# 14_Ethernet.net
KiCad netlist of a schematic drawn in Altium Designer
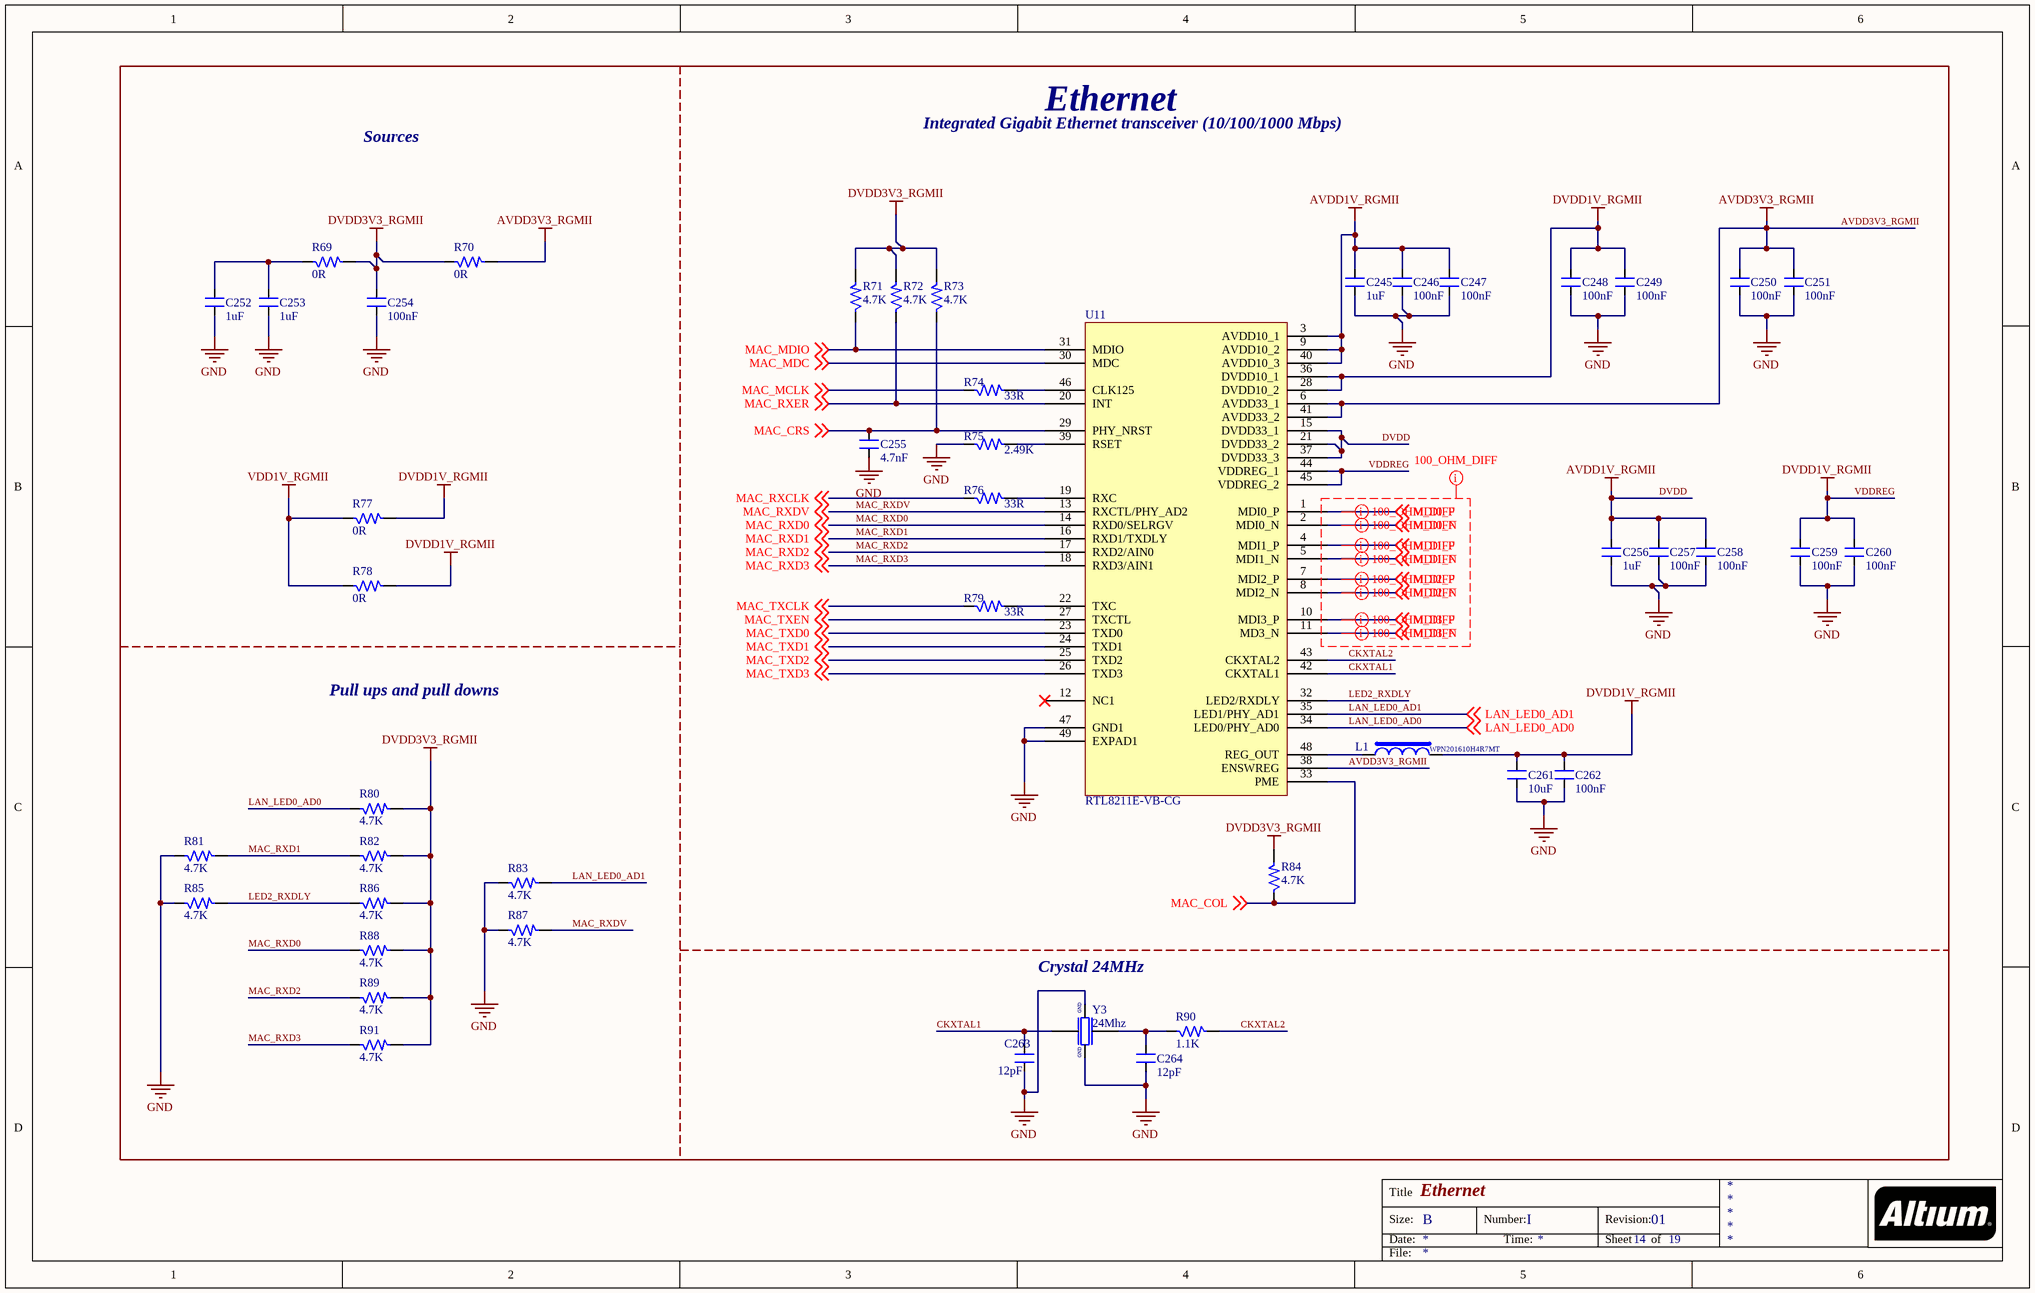
[diagram p0: [14] Ethernet.SchDoc]

(export (version "E")
  (design (tool "Eeschema 10.0.6"))
  (components
    (comp (ref "C245")
      (value "1uF")
      (footprint "CAP_0201")
      (description "1µF ±20% 16V Ceramic Capacitor X5R 0201 (0603 Metric)")
      (fields
        (field (name "MANUFACTURER") "Samsung Electro-Mechanics")
        (field (name "MANUFACTURER PART NUMBER") "CL03A105MO3NRNH")
      )
      (libsource (lib "EsteemPCB_SOM_Course_intlib") (part "CAP_1uF-16V-10%-0201"))
    )
    (comp (ref "C246")
      (value "100nF")
      (footprint "CAP_0201")
      (description "0.1µF ±10% 25V Ceramic Capacitor X5R 0201 (0603 Metric)")
      (fields
        (field (name "MANUFACTURER") "TDK Corporation")
        (field (name "MANUFACTURER PART NUMBER") "C0603X5R1E104K030BB")
      )
      (libsource (lib "EsteemPCB_SOM_Course_intlib") (part "CAP_100nF-25V-10%-0201"))
    )
    (comp (ref "C247")
      (value "100nF")
      (footprint "CAP_0201")
      (description "0.1µF ±10% 25V Ceramic Capacitor X5R 0201 (0603 Metric)")
      (fields
        (field (name "MANUFACTURER") "TDK Corporation")
        (field (name "MANUFACTURER PART NUMBER") "C0603X5R1E104K030BB")
      )
      (libsource (lib "EsteemPCB_SOM_Course_intlib") (part "CAP_100nF-25V-10%-0201"))
    )
    (comp (ref "C248")
      (value "100nF")
      (footprint "CAP_0201")
      (description "0.1µF ±10% 25V Ceramic Capacitor X5R 0201 (0603 Metric)")
      (fields
        (field (name "MANUFACTURER") "TDK Corporation")
        (field (name "MANUFACTURER PART NUMBER") "C0603X5R1E104K030BB")
      )
      (libsource (lib "EsteemPCB_SOM_Course_intlib") (part "CAP_100nF-25V-10%-0201"))
    )
    (comp (ref "C249")
      (value "100nF")
      (footprint "CAP_0201")
      (description "0.1µF ±10% 25V Ceramic Capacitor X5R 0201 (0603 Metric)")
      (fields
        (field (name "MANUFACTURER") "TDK Corporation")
        (field (name "MANUFACTURER PART NUMBER") "C0603X5R1E104K030BB")
      )
      (libsource (lib "EsteemPCB_SOM_Course_intlib") (part "CAP_100nF-25V-10%-0201"))
    )
    (comp (ref "C250")
      (value "100nF")
      (footprint "CAP_0201")
      (description "0.1µF ±10% 25V Ceramic Capacitor X5R 0201 (0603 Metric)")
      (fields
        (field (name "MANUFACTURER") "TDK Corporation")
        (field (name "MANUFACTURER PART NUMBER") "C0603X5R1E104K030BB")
      )
      (libsource (lib "EsteemPCB_SOM_Course_intlib") (part "CAP_100nF-25V-10%-0201"))
    )
    (comp (ref "C251")
      (value "100nF")
      (footprint "CAP_0201")
      (description "0.1µF ±10% 25V Ceramic Capacitor X5R 0201 (0603 Metric)")
      (fields
        (field (name "MANUFACTURER") "TDK Corporation")
        (field (name "MANUFACTURER PART NUMBER") "C0603X5R1E104K030BB")
      )
      (libsource (lib "EsteemPCB_SOM_Course_intlib") (part "CAP_100nF-25V-10%-0201"))
    )
    (comp (ref "C252")
      (value "1uF")
      (footprint "CAP_0402")
      (description "1µF ±10% 16V Ceramic Capacitor X5R 0402 (1005 Metric)")
      (fields
        (field (name "MANUFACTURER") "Knowles Novacap")
        (field (name "MANUFACTURER PART NUMBER") "0402BW105K160YT")
      )
      (libsource (lib "EsteemPCB_SOM_Course_intlib") (part "CAP_1uF-16V-10%-0402"))
    )
    (comp (ref "C253")
      (value "1uF")
      (footprint "CAP_0402")
      (description "1µF ±10% 16V Ceramic Capacitor X5R 0402 (1005 Metric)")
      (fields
        (field (name "MANUFACTURER") "Knowles Novacap")
        (field (name "MANUFACTURER PART NUMBER") "0402BW105K160YT")
      )
      (libsource (lib "EsteemPCB_SOM_Course_intlib") (part "CAP_1uF-16V-10%-0402"))
    )
    (comp (ref "C254")
      (value "100nF")
      (footprint "CAP_0201")
      (description "0.1µF ±10% 25V Ceramic Capacitor X5R 0201 (0603 Metric)")
      (fields
        (field (name "MANUFACTURER") "TDK Corporation")
        (field (name "MANUFACTURER PART NUMBER") "C0603X5R1E104K030BB")
      )
      (libsource (lib "EsteemPCB_SOM_Course_intlib") (part "CAP_100nF-25V-10%-0201"))
    )
    (comp (ref "C255")
      (value "4.7nF")
      (footprint "CAP_0201")
      (description "4700pF ±10% 10V Ceramic Capacitor X7R 0201 (0603 Metric)")
      (fields
        (field (name "MANUFACTURER") "AVX Corporation")
        (field (name "MANUFACTURER PART NUMBER") "0201ZC472KAT2A")
      )
      (libsource (lib "EsteemPCB_SOM_Course_intlib") (part "CAP_4.7nF-10V-10%-0201"))
    )
    (comp (ref "C256")
      (value "1uF")
      (footprint "CAP_0201")
      (description "1µF ±20% 16V Ceramic Capacitor X5R 0201 (0603 Metric)")
      (fields
        (field (name "MANUFACTURER") "Samsung Electro-Mechanics")
        (field (name "MANUFACTURER PART NUMBER") "CL03A105MO3NRNH")
      )
      (libsource (lib "EsteemPCB_SOM_Course_intlib") (part "CAP_1uF-16V-10%-0201"))
    )
    (comp (ref "C257")
      (value "100nF")
      (footprint "CAP_0201")
      (description "0.1µF ±10% 25V Ceramic Capacitor X5R 0201 (0603 Metric)")
      (fields
        (field (name "MANUFACTURER") "TDK Corporation")
        (field (name "MANUFACTURER PART NUMBER") "C0603X5R1E104K030BB")
      )
      (libsource (lib "EsteemPCB_SOM_Course_intlib") (part "CAP_100nF-25V-10%-0201"))
    )
    (comp (ref "C258")
      (value "100nF")
      (footprint "CAP_0201")
      (description "0.1µF ±10% 25V Ceramic Capacitor X5R 0201 (0603 Metric)")
      (fields
        (field (name "MANUFACTURER") "TDK Corporation")
        (field (name "MANUFACTURER PART NUMBER") "C0603X5R1E104K030BB")
      )
      (libsource (lib "EsteemPCB_SOM_Course_intlib") (part "CAP_100nF-25V-10%-0201"))
    )
    (comp (ref "C259")
      (value "100nF")
      (footprint "CAP_0201")
      (description "0.1µF ±10% 25V Ceramic Capacitor X5R 0201 (0603 Metric)")
      (fields
        (field (name "MANUFACTURER") "TDK Corporation")
        (field (name "MANUFACTURER PART NUMBER") "C0603X5R1E104K030BB")
      )
      (libsource (lib "EsteemPCB_SOM_Course_intlib") (part "CAP_100nF-25V-10%-0201"))
    )
    (comp (ref "C260")
      (value "100nF")
      (footprint "CAP_0201")
      (description "0.1µF ±10% 25V Ceramic Capacitor X5R 0201 (0603 Metric)")
      (fields
        (field (name "MANUFACTURER") "TDK Corporation")
        (field (name "MANUFACTURER PART NUMBER") "C0603X5R1E104K030BB")
      )
      (libsource (lib "EsteemPCB_SOM_Course_intlib") (part "CAP_100nF-25V-10%-0201"))
    )
    (comp (ref "C261")
      (value "10uF")
      (footprint "CAP_0402")
      (description "10µF ±20% 10V Ceramic Capacitor X5R 0402 (1005 Metric)")
      (fields
        (field (name "MANUFACTURER PART NUMBER") "CL05A106MP5NUNC")
        (field (name "MANUFACTURER") "Samsung Electro-Mechanics")
      )
      (libsource (lib "EsteemPCB_SOM_Course_intlib") (part "CAP_10uF-10V-20%-0402"))
    )
    (comp (ref "C262")
      (value "100nF")
      (footprint "CAP_0201")
      (description "0.1µF ±10% 25V Ceramic Capacitor X5R 0201 (0603 Metric)")
      (fields
        (field (name "MANUFACTURER") "TDK Corporation")
        (field (name "MANUFACTURER PART NUMBER") "C0603X5R1E104K030BB")
      )
      (libsource (lib "EsteemPCB_SOM_Course_intlib") (part "CAP_100nF-25V-10%-0201"))
    )
    (comp (ref "C263")
      (value "12pF")
      (footprint "CAP_0402")
      (description "12pF ±10% 10V Ceramic Capacitor X8R 0402 (1005 Metric)")
      (fields
        (field (name "MANUFACTURER") "KEMET")
        (field (name "MANUFACTURER PART NUMBER") "C0402C120K8HAC7867")
      )
      (libsource (lib "EsteemPCB_SOM_Course_intlib") (part "CAP_12pF-10V-10%-0402"))
    )
    (comp (ref "C264")
      (value "12pF")
      (footprint "CAP_0402")
      (description "12pF ±10% 10V Ceramic Capacitor X8R 0402 (1005 Metric)")
      (fields
        (field (name "MANUFACTURER") "KEMET")
        (field (name "MANUFACTURER PART NUMBER") "C0402C120K8HAC7867")
      )
      (libsource (lib "EsteemPCB_SOM_Course_intlib") (part "CAP_12pF-10V-10%-0402"))
    )
    (comp (ref "L1")
      (value "WPN201610H4R7MT")
      (footprint "IND_62.9_110X86.6_SMD")
      (description "4.7uH ±20% 900mA 425mΩ SMD,2.0x1.6x1.0mm Power Inductors RoHS")
      (fields (field (name "MANUFACTURER") "Sunlord"))
      (libsource (lib "EsteemPCB_SOM_Course_intlib") (part "IND_4.7uH-0.9A-20%-SMD"))
    )
    (comp (ref "R69")
      (value "0R")
      (footprint "RES_0201")
      (description "0 Ohms Jumper 0.05W, 1/20W Chip Resistor 0201 (0603 Metric) Automotive AEC-Q200 Thick Film")
      (fields
        (field (name "MANUFACTURER") "Bourns Inc.")
        (field (name "MANUFACTURER PART NUMBER") "CR0201AJ/-000GLF")
      )
      (libsource (lib "EsteemPCB_SOM_Course_intlib") (part "RES_0R-0.05W-1%-0201"))
    )
    (comp (ref "R70")
      (value "0R")
      (footprint "RES_0201")
      (description "0 Ohms Jumper 0.05W, 1/20W Chip Resistor 0201 (0603 Metric) Automotive AEC-Q200 Thick Film")
      (fields
        (field (name "MANUFACTURER") "Bourns Inc.")
        (field (name "MANUFACTURER PART NUMBER") "CR0201AJ/-000GLF")
      )
      (libsource (lib "EsteemPCB_SOM_Course_intlib") (part "RES_0R-0.05W-1%-0201"))
    )
    (comp (ref "R71")
      (value "4.7K")
      (footprint "RES_0201")
      (description "4.02 kOhms ±1% 0.05W, 1/20W Chip Resistor 0201 (0603 Metric) Thick Film")
      (fields
        (field (name "MANUFACTURER") "Yageo")
        (field (name "MANUFACTURER PART NUMBER") "RC0201FR-074K02L")
      )
      (libsource (lib "EsteemPCB_SOM_Course_intlib") (part "RES_4.7K-0.1W-1%-0201"))
    )
    (comp (ref "R72")
      (value "4.7K")
      (footprint "RES_0201")
      (description "4.02 kOhms ±1% 0.05W, 1/20W Chip Resistor 0201 (0603 Metric) Thick Film")
      (fields
        (field (name "MANUFACTURER") "Yageo")
        (field (name "MANUFACTURER PART NUMBER") "RC0201FR-074K02L")
      )
      (libsource (lib "EsteemPCB_SOM_Course_intlib") (part "RES_4.7K-0.1W-1%-0201"))
    )
    (comp (ref "R73")
      (value "4.7K")
      (footprint "RES_0201")
      (description "4.02 kOhms ±1% 0.05W, 1/20W Chip Resistor 0201 (0603 Metric) Thick Film")
      (fields
        (field (name "MANUFACTURER") "Yageo")
        (field (name "MANUFACTURER PART NUMBER") "RC0201FR-074K02L")
      )
      (libsource (lib "EsteemPCB_SOM_Course_intlib") (part "RES_4.7K-0.1W-1%-0201"))
    )
    (comp (ref "R74")
      (value "33R")
      (footprint "RES_0201")
      (description "33 Ohms ±1% 0.05W, 1/20W Chip Resistor 0201 (0603 Metric) Thick Film")
      (fields
        (field (name "MANUFACTURER") "Yageo")
        (field (name "MANUFACTURER PART NUMBER") "RC0201FR-0733RL")
      )
      (libsource (lib "EsteemPCB_SOM_Course_intlib") (part "RES_33R-0.05W-1%-0201"))
    )
    (comp (ref "R75")
      (value "2.49K")
      (footprint "RES_0201")
      (description "2.49 kOhms ±1% 0.05W, 1/20W Chip Resistor 0201 (0603 Metric) Automotive AEC-Q200 Thick Film")
      (fields
        (field (name "MANUFACTURER") "Panasonic Electronic Components")
        (field (name "MANUFACTURER PART NUMBER") "ERJ-1GNF2491C")
      )
      (libsource (lib "EsteemPCB_SOM_Course_intlib") (part "RES_2.49K-0.05W-1%-0201"))
    )
    (comp (ref "R76")
      (value "33R")
      (footprint "RES_0201")
      (description "33 Ohms ±1% 0.05W, 1/20W Chip Resistor 0201 (0603 Metric) Thick Film")
      (fields
        (field (name "MANUFACTURER") "Yageo")
        (field (name "MANUFACTURER PART NUMBER") "RC0201FR-0733RL")
      )
      (libsource (lib "EsteemPCB_SOM_Course_intlib") (part "RES_33R-0.05W-1%-0201"))
    )
    (comp (ref "R77")
      (value "0R")
      (footprint "RES_0201")
      (description "0 Ohms Jumper 0.05W, 1/20W Chip Resistor 0201 (0603 Metric) Automotive AEC-Q200 Thick Film")
      (fields
        (field (name "MANUFACTURER") "Bourns Inc.")
        (field (name "MANUFACTURER PART NUMBER") "CR0201AJ/-000GLF")
      )
      (libsource (lib "EsteemPCB_SOM_Course_intlib") (part "RES_0R-0.05W-1%-0201"))
    )
    (comp (ref "R78")
      (value "0R")
      (footprint "RES_0201")
      (description "0 Ohms Jumper 0.05W, 1/20W Chip Resistor 0201 (0603 Metric) Automotive AEC-Q200 Thick Film")
      (fields
        (field (name "MANUFACTURER") "Bourns Inc.")
        (field (name "MANUFACTURER PART NUMBER") "CR0201AJ/-000GLF")
      )
      (libsource (lib "EsteemPCB_SOM_Course_intlib") (part "RES_0R-0.05W-1%-0201"))
    )
    (comp (ref "R79")
      (value "33R")
      (footprint "RES_0201")
      (description "33 Ohms ±1% 0.05W, 1/20W Chip Resistor 0201 (0603 Metric) Thick Film")
      (fields
        (field (name "MANUFACTURER") "Yageo")
        (field (name "MANUFACTURER PART NUMBER") "RC0201FR-0733RL")
      )
      (libsource (lib "EsteemPCB_SOM_Course_intlib") (part "RES_33R-0.05W-1%-0201"))
    )
    (comp (ref "R80")
      (value "4.7K")
      (footprint "RES_0201")
      (description "4.02 kOhms ±1% 0.05W, 1/20W Chip Resistor 0201 (0603 Metric) Thick Film")
      (fields
        (field (name "MANUFACTURER") "Yageo")
        (field (name "MANUFACTURER PART NUMBER") "RC0201FR-074K02L")
      )
      (libsource (lib "EsteemPCB_SOM_Course_intlib") (part "RES_4.7K-0.1W-1%-0201"))
    )
    (comp (ref "R81")
      (value "4.7K")
      (footprint "RES_0201")
      (description "4.02 kOhms ±1% 0.05W, 1/20W Chip Resistor 0201 (0603 Metric) Thick Film")
      (fields
        (field (name "MANUFACTURER") "Yageo")
        (field (name "MANUFACTURER PART NUMBER") "RC0201FR-074K02L")
      )
      (libsource (lib "EsteemPCB_SOM_Course_intlib") (part "RES_4.7K-0.1W-1%-0201"))
    )
    (comp (ref "R82")
      (value "4.7K")
      (footprint "RES_0201")
      (description "4.02 kOhms ±1% 0.05W, 1/20W Chip Resistor 0201 (0603 Metric) Thick Film")
      (fields
        (field (name "MANUFACTURER") "Yageo")
        (field (name "MANUFACTURER PART NUMBER") "RC0201FR-074K02L")
      )
      (libsource (lib "EsteemPCB_SOM_Course_intlib") (part "RES_4.7K-0.1W-1%-0201"))
    )
    (comp (ref "R83")
      (value "4.7K")
      (footprint "RES_0201")
      (description "4.02 kOhms ±1% 0.05W, 1/20W Chip Resistor 0201 (0603 Metric) Thick Film")
      (fields
        (field (name "MANUFACTURER") "Yageo")
        (field (name "MANUFACTURER PART NUMBER") "RC0201FR-074K02L")
      )
      (libsource (lib "EsteemPCB_SOM_Course_intlib") (part "RES_4.7K-0.1W-1%-0201"))
    )
    (comp (ref "R84")
      (value "4.7K")
      (footprint "RES_0201")
      (description "4.02 kOhms ±1% 0.05W, 1/20W Chip Resistor 0201 (0603 Metric) Thick Film")
      (fields
        (field (name "MANUFACTURER") "Yageo")
        (field (name "MANUFACTURER PART NUMBER") "RC0201FR-074K02L")
      )
      (libsource (lib "EsteemPCB_SOM_Course_intlib") (part "RES_4.7K-0.1W-1%-0201"))
    )
    (comp (ref "R85")
      (value "4.7K")
      (footprint "RES_0201")
      (description "4.02 kOhms ±1% 0.05W, 1/20W Chip Resistor 0201 (0603 Metric) Thick Film")
      (fields
        (field (name "MANUFACTURER") "Yageo")
        (field (name "MANUFACTURER PART NUMBER") "RC0201FR-074K02L")
      )
      (libsource (lib "EsteemPCB_SOM_Course_intlib") (part "RES_4.7K-0.1W-1%-0201"))
    )
    (comp (ref "R86")
      (value "4.7K")
      (footprint "RES_0201")
      (description "4.02 kOhms ±1% 0.05W, 1/20W Chip Resistor 0201 (0603 Metric) Thick Film")
      (fields
        (field (name "MANUFACTURER") "Yageo")
        (field (name "MANUFACTURER PART NUMBER") "RC0201FR-074K02L")
      )
      (libsource (lib "EsteemPCB_SOM_Course_intlib") (part "RES_4.7K-0.1W-1%-0201"))
    )
    (comp (ref "R87")
      (value "4.7K")
      (footprint "RES_0201")
      (description "4.02 kOhms ±1% 0.05W, 1/20W Chip Resistor 0201 (0603 Metric) Thick Film")
      (fields
        (field (name "MANUFACTURER") "Yageo")
        (field (name "MANUFACTURER PART NUMBER") "RC0201FR-074K02L")
      )
      (libsource (lib "EsteemPCB_SOM_Course_intlib") (part "RES_4.7K-0.1W-1%-0201"))
    )
    (comp (ref "R88")
      (value "4.7K")
      (footprint "RES_0201")
      (description "4.02 kOhms ±1% 0.05W, 1/20W Chip Resistor 0201 (0603 Metric) Thick Film")
      (fields
        (field (name "MANUFACTURER") "Yageo")
        (field (name "MANUFACTURER PART NUMBER") "RC0201FR-074K02L")
      )
      (libsource (lib "EsteemPCB_SOM_Course_intlib") (part "RES_4.7K-0.1W-1%-0201"))
    )
    (comp (ref "R89")
      (value "4.7K")
      (footprint "RES_0201")
      (description "4.02 kOhms ±1% 0.05W, 1/20W Chip Resistor 0201 (0603 Metric) Thick Film")
      (fields
        (field (name "MANUFACTURER") "Yageo")
        (field (name "MANUFACTURER PART NUMBER") "RC0201FR-074K02L")
      )
      (libsource (lib "EsteemPCB_SOM_Course_intlib") (part "RES_4.7K-0.1W-1%-0201"))
    )
    (comp (ref "R90")
      (value "1.1K")
      (footprint "RES_0201")
      (description "1.1 kOhms ±1% 0.05W, 1/20W Chip Resistor 0201 (0603 Metric) Automotive AEC-Q200 Thick Film")
      (fields
        (field (name "MANUFACTURER") "Panasonic Electronic Components")
        (field (name "MANUFACTURER PART NUMBER") "ERJ-1GNF1101C")
      )
      (libsource (lib "EsteemPCB_SOM_Course_intlib") (part "RES_1.1K-0.05W-1%-0201"))
    )
    (comp (ref "R91")
      (value "4.7K")
      (footprint "RES_0201")
      (description "4.02 kOhms ±1% 0.05W, 1/20W Chip Resistor 0201 (0603 Metric) Thick Film")
      (fields
        (field (name "MANUFACTURER") "Yageo")
        (field (name "MANUFACTURER PART NUMBER") "RC0201FR-074K02L")
      )
      (libsource (lib "EsteemPCB_SOM_Course_intlib") (part "RES_4.7K-0.1W-1%-0201"))
    )
    (comp (ref "U11")
      (value "RTL8211E-VB-CG")
      (footprint "QFN48_19.6_324X324_SMD")
      (fields (field (name "MANUFACTURER") "Realtek Semicon"))
      (libsource (lib "EsteemPCB_SOM_Course_intlib") (part "IC_RTL8211E-VB-CG"))
    )
    (comp (ref "Y3")
      (value "24Mhz")
      (footprint "XTAL_ABM8AIG-24.000MHZ-12-2Z-T3")
      (description "24MHz ±20ppm Crystal 12pF 50 Ohms 4-SMD, No Lead")
      (fields
        (field (name "MANUFACTURER") "Abracon LLC")
        (field (name "MANUFACTURER PART NUMBER") "ABM8AIG-24.000MHZ-12-2Z-T3")
      )
      (libsource (lib "EsteemPCB_SOM_Course_intlib") (part "XTAL_24Mhz-12pF-4-SMD"))
    )
  )
  (nets
    (net (code "1") (name "/CKXTAL1") (class "Default")
      (node (ref "C263") (pin "2") (pinfunction "2_2") (pintype "passive"))
      (node (ref "U11") (pin "42") (pinfunction "CKXTAL1_42") (pintype "passive"))
      (node (ref "Y3") (pin "1") (pinfunction "1_1") (pintype "passive"))
    )
    (net (code "2") (name "/CKXTAL2") (class "Default")
      (node (ref "R90") (pin "2") (pinfunction "2_2") (pintype "passive"))
      (node (ref "U11") (pin "43") (pinfunction "CKXTAL2_43") (pintype "passive"))
    )
    (net (code "3") (name "/LED2_RXDLY") (class "Default")
      (node (ref "R85") (pin "2") (pinfunction "2_2") (pintype "passive"))
      (node (ref "R86") (pin "1") (pinfunction "1_1") (pintype "passive"))
      (node (ref "U11") (pin "32") (pinfunction "LED2/RXDLY_32") (pintype "passive"))
    )
    (net (code "4") (name "AVDD1V_RGMII") (class "Default")
      (node (ref "C245") (pin "2") (pinfunction "2_2") (pintype "passive"))
      (node (ref "C246") (pin "2") (pinfunction "2_2") (pintype "passive"))
      (node (ref "C247") (pin "2") (pinfunction "2_2") (pintype "passive"))
      (node (ref "C256") (pin "2") (pinfunction "2_2") (pintype "passive"))
      (node (ref "C257") (pin "2") (pinfunction "2_2") (pintype "passive"))
      (node (ref "C258") (pin "2") (pinfunction "2_2") (pintype "passive"))
      (node (ref "U11") (pin "15") (pinfunction "DVDD33_1_15") (pintype "passive"))
      (node (ref "U11") (pin "21") (pinfunction "DVDD33_2_21") (pintype "passive"))
      (node (ref "U11") (pin "3") (pinfunction "AVDD10_1_3") (pintype "passive"))
      (node (ref "U11") (pin "37") (pinfunction "DVDD33_3_37") (pintype "passive"))
      (node (ref "U11") (pin "40") (pinfunction "AVDD10_3_40") (pintype "passive"))
      (node (ref "U11") (pin "9") (pinfunction "AVDD10_2_9") (pintype "passive"))
    )
    (net (code "5") (name "AVDD3V3_RGMII") (class "Default")
      (node (ref "C250") (pin "2") (pinfunction "2_2") (pintype "passive"))
      (node (ref "C251") (pin "2") (pinfunction "2_2") (pintype "passive"))
      (node (ref "R70") (pin "2") (pinfunction "2_2") (pintype "passive"))
      (node (ref "U11") (pin "38") (pinfunction "ENSWREG_38") (pintype "passive"))
      (node (ref "U11") (pin "41") (pinfunction "AVDD33_2_41") (pintype "passive"))
      (node (ref "U11") (pin "6") (pinfunction "AVDD33_1_6") (pintype "passive"))
    )
    (net (code "6") (name "DVDD1V_RGMII") (class "Default")
      (node (ref "C248") (pin "2") (pinfunction "2_2") (pintype "passive"))
      (node (ref "C249") (pin "2") (pinfunction "2_2") (pintype "passive"))
      (node (ref "C259") (pin "2") (pinfunction "2_2") (pintype "passive"))
      (node (ref "C260") (pin "2") (pinfunction "2_2") (pintype "passive"))
      (node (ref "C261") (pin "2") (pinfunction "2_2") (pintype "passive"))
      (node (ref "C262") (pin "2") (pinfunction "2_2") (pintype "passive"))
      (node (ref "L1") (pin "2") (pinfunction "2_2") (pintype "passive"))
      (node (ref "R77") (pin "2") (pinfunction "2_2") (pintype "passive"))
      (node (ref "R78") (pin "2") (pinfunction "2_2") (pintype "passive"))
      (node (ref "U11") (pin "28") (pinfunction "DVDD10_2_28") (pintype "passive"))
      (node (ref "U11") (pin "36") (pinfunction "DVDD10_1_36") (pintype "passive"))
      (node (ref "U11") (pin "44") (pinfunction "VDDREG_1_44") (pintype "passive"))
      (node (ref "U11") (pin "45") (pinfunction "VDDREG_2_45") (pintype "passive"))
    )
    (net (code "7") (name "DVDD3V3_RGMII") (class "Default")
      (node (ref "C254") (pin "2") (pinfunction "2_2") (pintype "passive"))
      (node (ref "R69") (pin "2") (pinfunction "2_2") (pintype "passive"))
      (node (ref "R70") (pin "1") (pinfunction "1_1") (pintype "passive"))
      (node (ref "R71") (pin "2") (pinfunction "2_2") (pintype "passive"))
      (node (ref "R72") (pin "2") (pinfunction "2_2") (pintype "passive"))
      (node (ref "R73") (pin "2") (pinfunction "2_2") (pintype "passive"))
      (node (ref "R80") (pin "2") (pinfunction "2_2") (pintype "passive"))
      (node (ref "R82") (pin "2") (pinfunction "2_2") (pintype "passive"))
      (node (ref "R84") (pin "2") (pinfunction "2_2") (pintype "passive"))
      (node (ref "R86") (pin "2") (pinfunction "2_2") (pintype "passive"))
      (node (ref "R88") (pin "2") (pinfunction "2_2") (pintype "passive"))
      (node (ref "R89") (pin "2") (pinfunction "2_2") (pintype "passive"))
      (node (ref "R91") (pin "2") (pinfunction "2_2") (pintype "passive"))
    )
    (net (code "8") (name "GND") (class "Default")
      (node (ref "C245") (pin "1") (pinfunction "1_1") (pintype "passive"))
      (node (ref "C246") (pin "1") (pinfunction "1_1") (pintype "passive"))
      (node (ref "C247") (pin "1") (pinfunction "1_1") (pintype "passive"))
      (node (ref "C248") (pin "1") (pinfunction "1_1") (pintype "passive"))
      (node (ref "C249") (pin "1") (pinfunction "1_1") (pintype "passive"))
      (node (ref "C250") (pin "1") (pinfunction "1_1") (pintype "passive"))
      (node (ref "C251") (pin "1") (pinfunction "1_1") (pintype "passive"))
      (node (ref "C252") (pin "1") (pinfunction "1_1") (pintype "passive"))
      (node (ref "C253") (pin "1") (pinfunction "1_1") (pintype "passive"))
      (node (ref "C254") (pin "1") (pinfunction "1_1") (pintype "passive"))
      (node (ref "C255") (pin "1") (pinfunction "1_1") (pintype "passive"))
      (node (ref "C256") (pin "1") (pinfunction "1_1") (pintype "passive"))
      (node (ref "C257") (pin "1") (pinfunction "1_1") (pintype "passive"))
      (node (ref "C258") (pin "1") (pinfunction "1_1") (pintype "passive"))
      (node (ref "C259") (pin "1") (pinfunction "1_1") (pintype "passive"))
      (node (ref "C260") (pin "1") (pinfunction "1_1") (pintype "passive"))
      (node (ref "C261") (pin "1") (pinfunction "1_1") (pintype "passive"))
      (node (ref "C262") (pin "1") (pinfunction "1_1") (pintype "passive"))
      (node (ref "C263") (pin "1") (pinfunction "1_1") (pintype "passive"))
      (node (ref "C264") (pin "1") (pinfunction "1_1") (pintype "passive"))
      (node (ref "R75") (pin "1") (pinfunction "1_1") (pintype "passive"))
      (node (ref "R81") (pin "1") (pinfunction "1_1") (pintype "passive"))
      (node (ref "R83") (pin "1") (pinfunction "1_1") (pintype "passive"))
      (node (ref "R85") (pin "1") (pinfunction "1_1") (pintype "passive"))
      (node (ref "R87") (pin "1") (pinfunction "1_1") (pintype "passive"))
      (node (ref "U11") (pin "47") (pinfunction "GND1_47") (pintype "passive"))
      (node (ref "U11") (pin "49") (pinfunction "EXPAD1_49") (pintype "passive"))
      (node (ref "Y3") (pin "2") (pinfunction "2_2") (pintype "passive"))
      (node (ref "Y3") (pin "4") (pinfunction "4_4") (pintype "passive"))
    )
    (net (code "9") (name "LAN_LED0_AD0") (class "Default")
      (node (ref "R80") (pin "1") (pinfunction "1_1") (pintype "passive"))
      (node (ref "U11") (pin "34") (pinfunction "LED0/PHY_AD0_34") (pintype "passive"))
    )
    (net (code "10") (name "LAN_LED0_AD1") (class "Default")
      (node (ref "R83") (pin "2") (pinfunction "2_2") (pintype "passive"))
      (node (ref "U11") (pin "35") (pinfunction "LED1/PHY_AD1_35") (pintype "passive"))
    )
    (net (code "11") (name "MAC_COL") (class "Default")
      (node (ref "R84") (pin "1") (pinfunction "1_1") (pintype "passive"))
      (node (ref "U11") (pin "33") (pinfunction "PME_33") (pintype "passive"))
    )
    (net (code "12") (name "MAC_CRS") (class "Default")
      (node (ref "C255") (pin "2") (pinfunction "2_2") (pintype "passive"))
      (node (ref "R73") (pin "1") (pinfunction "1_1") (pintype "passive"))
      (node (ref "U11") (pin "29") (pinfunction "PHY_NRST_29") (pintype "passive"))
    )
    (net (code "13") (name "MAC_MCLK") (class "Default")
      (node (ref "R74") (pin "1") (pinfunction "1_1") (pintype "passive"))
    )
    (net (code "14") (name "MAC_MDC") (class "Default")
      (node (ref "U11") (pin "30") (pinfunction "MDC_30") (pintype "passive"))
    )
    (net (code "15") (name "MAC_MDIO") (class "Default")
      (node (ref "R71") (pin "1") (pinfunction "1_1") (pintype "passive"))
      (node (ref "U11") (pin "31") (pinfunction "MDIO_31") (pintype "passive"))
    )
    (net (code "16") (name "MAC_RXCLK") (class "Default")
      (node (ref "R76") (pin "1") (pinfunction "1_1") (pintype "passive"))
    )
    (net (code "17") (name "MAC_RXD0") (class "Default")
      (node (ref "R88") (pin "1") (pinfunction "1_1") (pintype "passive"))
      (node (ref "U11") (pin "14") (pinfunction "RXD0/SELRGV_14") (pintype "passive"))
    )
    (net (code "18") (name "MAC_RXD1") (class "Default")
      (node (ref "R81") (pin "2") (pinfunction "2_2") (pintype "passive"))
      (node (ref "R82") (pin "1") (pinfunction "1_1") (pintype "passive"))
      (node (ref "U11") (pin "16") (pinfunction "RXD1/TXDLY_16") (pintype "passive"))
    )
    (net (code "19") (name "MAC_RXD2") (class "Default")
      (node (ref "R89") (pin "1") (pinfunction "1_1") (pintype "passive"))
      (node (ref "U11") (pin "17") (pinfunction "RXD2/AIN0_17") (pintype "passive"))
    )
    (net (code "20") (name "MAC_RXD3") (class "Default")
      (node (ref "R91") (pin "1") (pinfunction "1_1") (pintype "passive"))
      (node (ref "U11") (pin "18") (pinfunction "RXD3/AIN1_18") (pintype "passive"))
    )
    (net (code "21") (name "MAC_RXDV") (class "Default")
      (node (ref "R87") (pin "2") (pinfunction "2_2") (pintype "passive"))
      (node (ref "U11") (pin "13") (pinfunction "RXCTL/PHY_AD2_13") (pintype "passive"))
    )
    (net (code "22") (name "MAC_RXER") (class "Default")
      (node (ref "R72") (pin "1") (pinfunction "1_1") (pintype "passive"))
      (node (ref "U11") (pin "20") (pinfunction "INT_20") (pintype "passive"))
    )
    (net (code "23") (name "MAC_TXCLK") (class "Default")
      (node (ref "R79") (pin "1") (pinfunction "1_1") (pintype "passive"))
    )
    (net (code "24") (name "MAC_TXD0") (class "Default")
      (node (ref "U11") (pin "23") (pinfunction "TXD0_23") (pintype "passive"))
    )
    (net (code "25") (name "MAC_TXD1") (class "Default")
      (node (ref "U11") (pin "24") (pinfunction "TXD1_24") (pintype "passive"))
    )
    (net (code "26") (name "MAC_TXD2") (class "Default")
      (node (ref "U11") (pin "25") (pinfunction "TXD2_25") (pintype "passive"))
    )
    (net (code "27") (name "MAC_TXD3") (class "Default")
      (node (ref "U11") (pin "26") (pinfunction "TXD3_26") (pintype "passive"))
    )
    (net (code "28") (name "MAC_TXEN") (class "Default")
      (node (ref "U11") (pin "27") (pinfunction "TXCTL_27") (pintype "passive"))
    )
    (net (code "29") (name "MDI0_N") (class "Default")
      (node (ref "U11") (pin "2") (pinfunction "MDI0_N_2") (pintype "passive"))
    )
    (net (code "30") (name "MDI0_P") (class "Default")
      (node (ref "U11") (pin "1") (pinfunction "MDI0_P_1") (pintype "passive"))
    )
    (net (code "31") (name "MDI1_N") (class "Default")
      (node (ref "U11") (pin "5") (pinfunction "MDI1_N_5") (pintype "passive"))
    )
    (net (code "32") (name "MDI1_P") (class "Default")
      (node (ref "U11") (pin "4") (pinfunction "MDI1_P_4") (pintype "passive"))
    )
    (net (code "33") (name "MDI2_N") (class "Default")
      (node (ref "U11") (pin "8") (pinfunction "MDI2_N_8") (pintype "passive"))
    )
    (net (code "34") (name "MDI2_P") (class "Default")
      (node (ref "U11") (pin "7") (pinfunction "MDI2_P_7") (pintype "passive"))
    )
    (net (code "35") (name "MDI3_N") (class "Default")
      (node (ref "U11") (pin "11") (pinfunction "MD3_N_11") (pintype "passive"))
    )
    (net (code "36") (name "MDI3_P") (class "Default")
      (node (ref "U11") (pin "10") (pinfunction "MDI3_P_10") (pintype "passive"))
    )
    (net (code "37") (name "Net-(C252-Pad2)") (class "Default")
      (node (ref "C252") (pin "2") (pinfunction "2_2") (pintype "passive"))
      (node (ref "C253") (pin "2") (pinfunction "2_2") (pintype "passive"))
      (node (ref "R69") (pin "1") (pinfunction "1_1") (pintype "passive"))
    )
    (net (code "38") (name "Net-(C264-Pad2)") (class "Default")
      (node (ref "C264") (pin "2") (pinfunction "2_2") (pintype "passive"))
      (node (ref "R90") (pin "1") (pinfunction "1_1") (pintype "passive"))
      (node (ref "Y3") (pin "3") (pinfunction "3_3") (pintype "passive"))
    )
    (net (code "39") (name "Net-(U11-CLK125)") (class "Default")
      (node (ref "R74") (pin "2") (pinfunction "2_2") (pintype "passive"))
      (node (ref "U11") (pin "46") (pinfunction "CLK125_46") (pintype "passive"))
    )
    (net (code "40") (name "Net-(U11-REG_OUT)") (class "Default")
      (node (ref "L1") (pin "1") (pinfunction "1_1") (pintype "passive"))
      (node (ref "U11") (pin "48") (pinfunction "REG_OUT_48") (pintype "passive"))
    )
    (net (code "41") (name "Net-(U11-RSET)") (class "Default")
      (node (ref "R75") (pin "2") (pinfunction "2_2") (pintype "passive"))
      (node (ref "U11") (pin "39") (pinfunction "RSET_39") (pintype "passive"))
    )
    (net (code "42") (name "Net-(U11-RXC)") (class "Default")
      (node (ref "R76") (pin "2") (pinfunction "2_2") (pintype "passive"))
      (node (ref "U11") (pin "19") (pinfunction "RXC_19") (pintype "passive"))
    )
    (net (code "43") (name "Net-(U11-TXC)") (class "Default")
      (node (ref "R79") (pin "2") (pinfunction "2_2") (pintype "passive"))
      (node (ref "U11") (pin "22") (pinfunction "TXC_22") (pintype "passive"))
    )
    (net (code "44") (name "VDD1V_RGMII") (class "Default")
      (node (ref "R77") (pin "1") (pinfunction "1_1") (pintype "passive"))
      (node (ref "R78") (pin "1") (pinfunction "1_1") (pintype "passive"))
    )
    (net (code "45") (name "unconnected-(U11-NC1-Pad12)") (class "Default")
      (node (ref "U11") (pin "12") (pinfunction "NC1_12") (pintype "passive+no_connect"))
    )
  )
)
